# PCB.net
KiCad netlist of a schematic drawn in Altium Designer
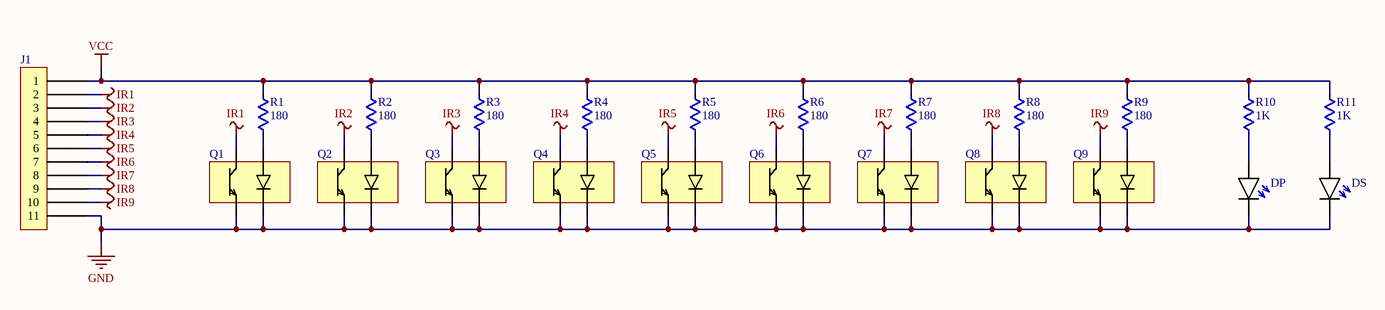
[diagram p0: PCB.SchDoc]

(export (version "E")
  (design (tool "Eeschema 10.0.6"))
  (components
    (comp (ref "DP") (value "LED") (footprint "LED-3MM-RED") (libsource (lib "AltiumLibrary") (part "LED")))
    (comp (ref "DS") (value "LED") (footprint "LED-3MM-GREEN") (libsource (lib "AltiumLibrary") (part "LED")))
    (comp (ref "J1")
      (value "Header 1x11")
      (footprint "Header 1x11")
      (libsource (lib "AltiumLibrary") (part "Header 1x11"))
    )
    (comp (ref "Q1")
      (value "QRE1113GR")
      (footprint "QRE1113GR")
      (fields (field (name "MF") "ON Semiconductor"))
      (libsource (lib "AltiumLibrary") (part "QRE1113GR"))
    )
    (comp (ref "Q2")
      (value "QRE1113GR")
      (footprint "QRE1113GR")
      (fields (field (name "MF") "ON Semiconductor"))
      (libsource (lib "AltiumLibrary") (part "QRE1113GR"))
    )
    (comp (ref "Q3")
      (value "QRE1113GR")
      (footprint "QRE1113GR")
      (fields (field (name "MF") "ON Semiconductor"))
      (libsource (lib "AltiumLibrary") (part "QRE1113GR"))
    )
    (comp (ref "Q4")
      (value "QRE1113GR")
      (footprint "QRE1113GR")
      (fields (field (name "MF") "ON Semiconductor"))
      (libsource (lib "AltiumLibrary") (part "QRE1113GR"))
    )
    (comp (ref "Q5")
      (value "QRE1113GR")
      (footprint "QRE1113GR")
      (fields (field (name "MF") "ON Semiconductor"))
      (libsource (lib "AltiumLibrary") (part "QRE1113GR"))
    )
    (comp (ref "Q6")
      (value "QRE1113GR")
      (footprint "QRE1113GR")
      (fields (field (name "MF") "ON Semiconductor"))
      (libsource (lib "AltiumLibrary") (part "QRE1113GR"))
    )
    (comp (ref "Q7")
      (value "QRE1113GR")
      (footprint "QRE1113GR")
      (fields (field (name "MF") "ON Semiconductor"))
      (libsource (lib "AltiumLibrary") (part "QRE1113GR"))
    )
    (comp (ref "Q8")
      (value "QRE1113GR")
      (footprint "QRE1113GR")
      (fields (field (name "MF") "ON Semiconductor"))
      (libsource (lib "AltiumLibrary") (part "QRE1113GR"))
    )
    (comp (ref "Q9")
      (value "QRE1113GR")
      (footprint "QRE1113GR")
      (fields (field (name "MF") "ON Semiconductor"))
      (libsource (lib "AltiumLibrary") (part "QRE1113GR"))
    )
    (comp (ref "R1")
      (value "180")
      (footprint "R1206")
      (fields (field (name "Comment") "RES"))
      (libsource (lib "AltiumLibrary") (part "RES"))
    )
    (comp (ref "R2")
      (value "180")
      (footprint "R1206")
      (fields (field (name "Comment") "RES"))
      (libsource (lib "AltiumLibrary") (part "RES"))
    )
    (comp (ref "R3")
      (value "180")
      (footprint "R1206")
      (fields (field (name "Comment") "RES"))
      (libsource (lib "AltiumLibrary") (part "RES"))
    )
    (comp (ref "R4")
      (value "180")
      (footprint "R1206")
      (fields (field (name "Comment") "RES"))
      (libsource (lib "AltiumLibrary") (part "RES"))
    )
    (comp (ref "R5")
      (value "180")
      (footprint "R1206")
      (fields (field (name "Comment") "RES"))
      (libsource (lib "AltiumLibrary") (part "RES"))
    )
    (comp (ref "R6")
      (value "180")
      (footprint "R1206")
      (fields (field (name "Comment") "RES"))
      (libsource (lib "AltiumLibrary") (part "RES"))
    )
    (comp (ref "R7")
      (value "180")
      (footprint "R1206")
      (fields (field (name "Comment") "RES"))
      (libsource (lib "AltiumLibrary") (part "RES"))
    )
    (comp (ref "R8")
      (value "180")
      (footprint "R1206")
      (fields (field (name "Comment") "RES"))
      (libsource (lib "AltiumLibrary") (part "RES"))
    )
    (comp (ref "R9")
      (value "180")
      (footprint "R1206")
      (fields (field (name "Comment") "RES"))
      (libsource (lib "AltiumLibrary") (part "RES"))
    )
    (comp (ref "R10")
      (value "1K")
      (footprint "R1206")
      (fields (field (name "Comment") "RES"))
      (libsource (lib "AltiumLibrary") (part "RES"))
    )
    (comp (ref "R11")
      (value "1K")
      (footprint "R1206")
      (fields (field (name "Comment") "RES"))
      (libsource (lib "AltiumLibrary") (part "RES"))
    )
  )
  (nets
    (net (code "1") (name "GND") (class "Default")
      (node (ref "DP") (pin "K") (pintype "passive"))
      (node (ref "DS") (pin "K") (pintype "passive"))
      (node (ref "J1") (pin "11") (pinfunction "11_11") (pintype "passive"))
      (node (ref "Q1") (pin "E") (pinfunction "E_E") (pintype "passive"))
      (node (ref "Q1") (pin "K") (pinfunction "K_K") (pintype "passive"))
      (node (ref "Q2") (pin "E") (pinfunction "E_E") (pintype "passive"))
      (node (ref "Q2") (pin "K") (pinfunction "K_K") (pintype "passive"))
      (node (ref "Q3") (pin "E") (pinfunction "E_E") (pintype "passive"))
      (node (ref "Q3") (pin "K") (pinfunction "K_K") (pintype "passive"))
      (node (ref "Q4") (pin "E") (pinfunction "E_E") (pintype "passive"))
      (node (ref "Q4") (pin "K") (pinfunction "K_K") (pintype "passive"))
      (node (ref "Q5") (pin "E") (pinfunction "E_E") (pintype "passive"))
      (node (ref "Q5") (pin "K") (pinfunction "K_K") (pintype "passive"))
      (node (ref "Q6") (pin "E") (pinfunction "E_E") (pintype "passive"))
      (node (ref "Q6") (pin "K") (pinfunction "K_K") (pintype "passive"))
      (node (ref "Q7") (pin "E") (pinfunction "E_E") (pintype "passive"))
      (node (ref "Q7") (pin "K") (pinfunction "K_K") (pintype "passive"))
      (node (ref "Q8") (pin "E") (pinfunction "E_E") (pintype "passive"))
      (node (ref "Q8") (pin "K") (pinfunction "K_K") (pintype "passive"))
      (node (ref "Q9") (pin "E") (pinfunction "E_E") (pintype "passive"))
      (node (ref "Q9") (pin "K") (pinfunction "K_K") (pintype "passive"))
    )
    (net (code "2") (name "IR1") (class "Default")
      (node (ref "J1") (pin "2") (pinfunction "2_2") (pintype "passive"))
      (node (ref "Q1") (pin "C") (pinfunction "C_C") (pintype "passive"))
    )
    (net (code "3") (name "IR2") (class "Default")
      (node (ref "J1") (pin "3") (pinfunction "3_3") (pintype "passive"))
      (node (ref "Q2") (pin "C") (pinfunction "C_C") (pintype "passive"))
    )
    (net (code "4") (name "IR3") (class "Default")
      (node (ref "J1") (pin "4") (pinfunction "4_4") (pintype "passive"))
      (node (ref "Q3") (pin "C") (pinfunction "C_C") (pintype "passive"))
    )
    (net (code "5") (name "IR4") (class "Default")
      (node (ref "J1") (pin "5") (pinfunction "5_5") (pintype "passive"))
      (node (ref "Q4") (pin "C") (pinfunction "C_C") (pintype "passive"))
    )
    (net (code "6") (name "IR5") (class "Default")
      (node (ref "J1") (pin "6") (pinfunction "6_6") (pintype "passive"))
      (node (ref "Q5") (pin "C") (pinfunction "C_C") (pintype "passive"))
    )
    (net (code "7") (name "IR6") (class "Default")
      (node (ref "J1") (pin "7") (pinfunction "7_7") (pintype "passive"))
      (node (ref "Q6") (pin "C") (pinfunction "C_C") (pintype "passive"))
    )
    (net (code "8") (name "IR7") (class "Default")
      (node (ref "J1") (pin "8") (pinfunction "8_8") (pintype "passive"))
      (node (ref "Q7") (pin "C") (pinfunction "C_C") (pintype "passive"))
    )
    (net (code "9") (name "IR8") (class "Default")
      (node (ref "J1") (pin "9") (pinfunction "9_9") (pintype "passive"))
      (node (ref "Q8") (pin "C") (pinfunction "C_C") (pintype "passive"))
    )
    (net (code "10") (name "IR9") (class "Default")
      (node (ref "J1") (pin "10") (pinfunction "10_10") (pintype "passive"))
      (node (ref "Q9") (pin "C") (pinfunction "C_C") (pintype "passive"))
    )
    (net (code "11") (name "Net-(DP-PadA)") (class "Default")
      (node (ref "DP") (pin "A") (pintype "passive"))
      (node (ref "R10") (pin "1") (pintype "passive"))
    )
    (net (code "12") (name "Net-(DS-PadA)") (class "Default")
      (node (ref "DS") (pin "A") (pintype "passive"))
      (node (ref "R11") (pin "1") (pintype "passive"))
    )
    (net (code "13") (name "Net-(Q1-PadA)") (class "Default")
      (node (ref "Q1") (pin "A") (pinfunction "A_A") (pintype "passive"))
      (node (ref "R1") (pin "1") (pintype "passive"))
    )
    (net (code "14") (name "Net-(Q2-PadA)") (class "Default")
      (node (ref "Q2") (pin "A") (pinfunction "A_A") (pintype "passive"))
      (node (ref "R2") (pin "1") (pintype "passive"))
    )
    (net (code "15") (name "Net-(Q3-PadA)") (class "Default")
      (node (ref "Q3") (pin "A") (pinfunction "A_A") (pintype "passive"))
      (node (ref "R3") (pin "1") (pintype "passive"))
    )
    (net (code "16") (name "Net-(Q4-PadA)") (class "Default")
      (node (ref "Q4") (pin "A") (pinfunction "A_A") (pintype "passive"))
      (node (ref "R4") (pin "1") (pintype "passive"))
    )
    (net (code "17") (name "Net-(Q5-PadA)") (class "Default")
      (node (ref "Q5") (pin "A") (pinfunction "A_A") (pintype "passive"))
      (node (ref "R5") (pin "1") (pintype "passive"))
    )
    (net (code "18") (name "Net-(Q6-PadA)") (class "Default")
      (node (ref "Q6") (pin "A") (pinfunction "A_A") (pintype "passive"))
      (node (ref "R6") (pin "1") (pintype "passive"))
    )
    (net (code "19") (name "Net-(Q7-PadA)") (class "Default")
      (node (ref "Q7") (pin "A") (pinfunction "A_A") (pintype "passive"))
      (node (ref "R7") (pin "1") (pintype "passive"))
    )
    (net (code "20") (name "Net-(Q8-PadA)") (class "Default")
      (node (ref "Q8") (pin "A") (pinfunction "A_A") (pintype "passive"))
      (node (ref "R8") (pin "1") (pintype "passive"))
    )
    (net (code "21") (name "Net-(Q9-PadA)") (class "Default")
      (node (ref "Q9") (pin "A") (pinfunction "A_A") (pintype "passive"))
      (node (ref "R9") (pin "1") (pintype "passive"))
    )
    (net (code "22") (name "VCC") (class "Default")
      (node (ref "J1") (pin "1") (pinfunction "1_1") (pintype "passive"))
      (node (ref "R1") (pin "2") (pintype "passive"))
      (node (ref "R10") (pin "2") (pintype "passive"))
      (node (ref "R11") (pin "2") (pintype "passive"))
      (node (ref "R2") (pin "2") (pintype "passive"))
      (node (ref "R3") (pin "2") (pintype "passive"))
      (node (ref "R4") (pin "2") (pintype "passive"))
      (node (ref "R5") (pin "2") (pintype "passive"))
      (node (ref "R6") (pin "2") (pintype "passive"))
      (node (ref "R7") (pin "2") (pintype "passive"))
      (node (ref "R8") (pin "2") (pintype "passive"))
      (node (ref "R9") (pin "2") (pintype "passive"))
    )
  )
)
